# Sheet1.net
KiCad netlist of a schematic drawn in Altium Designer
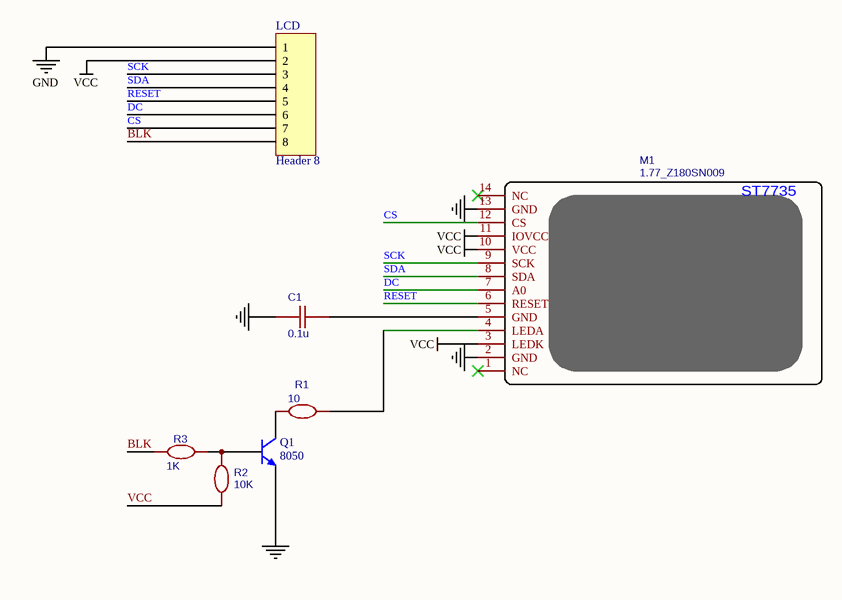
[diagram p0: Sheet1.SchDoc]

(export (version "E")
  (design (tool "Eeschema 10.0.6"))
  (components
    (comp (ref "C1")
      (value "0.1u")
      (footprint "0603")
      (fields (field (name "CONTRIBUTOR") "LCEDA_Lib"))
      (libsource (lib "altium-import") (part "root_2_0.1u_"))
    )
    (comp (ref "LCD")
      (value "Header 8")
      (footprint "HDR1X8")
      (description "Header, 8-Pin")
      (fields (field (name "PUBLISHER") "Altium Limited"))
      (libsource (lib "Miscellaneous Connectors") (part "Header 8"))
    )
    (comp (ref "M1")
      (value "1.77_Z180SN009")
      (footprint "PCBComponent_1")
      (fields (field (name "CONTRIBUTOR") "私有工程"))
      (libsource (lib "altium-import") (part "root_0_1.77_Z180SN009_"))
    )
    (comp (ref "Q1")
      (value "8050")
      (footprint "PCBComponent_1 - duplicate")
      (description "NPN General Purpose Amplifier")
      (fields (field (name "PUBLISHER") "Altium Limited"))
      (libsource (lib "Miscellaneous Devices") (part "2N3904"))
    )
    (comp (ref "R1")
      (value "10")
      (footprint "0603")
      (fields (field (name "CONTRIBUTOR") "LCEDA_Lib"))
      (libsource (lib "altium-import") (part "root_0_180R_"))
    )
    (comp (ref "R2")
      (value "10K")
      (footprint "0603")
      (fields (field (name "CONTRIBUTOR") "LCEDA_Lib"))
      (libsource (lib "altium-import") (part "root_1_0R/10K_"))
    )
    (comp (ref "R3")
      (value "1K")
      (footprint "0603")
      (fields (field (name "CONTRIBUTOR") "LCEDA_Lib"))
      (libsource (lib "altium-import") (part "root_2_470R_"))
    )
  )
  (nets
    (net (code "1") (name "/BLK") (class "Default")
      (node (ref "LCD") (pin "8") (pinfunction "8_8") (pintype "passive"))
      (node (ref "R3") (pin "2") (pinfunction "2_2") (pintype "passive"))
    )
    (net (code "2") (name "/CS") (class "Default")
      (node (ref "LCD") (pin "7") (pinfunction "7_7") (pintype "passive"))
      (node (ref "M1") (pin "12") (pinfunction "CS_12") (pintype "passive"))
    )
    (net (code "3") (name "/DC") (class "Default")
      (node (ref "LCD") (pin "6") (pinfunction "6_6") (pintype "passive"))
      (node (ref "M1") (pin "7") (pinfunction "A0_7") (pintype "passive"))
    )
    (net (code "4") (name "/RESET") (class "Default")
      (node (ref "LCD") (pin "5") (pinfunction "5_5") (pintype "passive"))
      (node (ref "M1") (pin "6") (pinfunction "RESET_6") (pintype "passive"))
    )
    (net (code "5") (name "/SCK") (class "Default")
      (node (ref "LCD") (pin "3") (pinfunction "3_3") (pintype "passive"))
      (node (ref "M1") (pin "9") (pinfunction "SCK_9") (pintype "passive"))
    )
    (net (code "6") (name "/SDA") (class "Default")
      (node (ref "LCD") (pin "4") (pinfunction "4_4") (pintype "passive"))
      (node (ref "M1") (pin "8") (pinfunction "SDA_8") (pintype "passive"))
    )
    (net (code "7") (name "GND") (class "Default")
      (node (ref "C1") (pin "2") (pinfunction "2_2") (pintype "passive"))
      (node (ref "LCD") (pin "1") (pinfunction "1_1") (pintype "passive"))
      (node (ref "M1") (pin "13") (pinfunction "GND_13") (pintype "passive"))
      (node (ref "M1") (pin "2") (pinfunction "GND_2") (pintype "passive"))
      (node (ref "Q1") (pin "1") (pinfunction "E_1") (pintype "passive"))
    )
    (net (code "8") (name "Net-(C1-Pad1)") (class "Default")
      (node (ref "C1") (pin "1") (pinfunction "1_1") (pintype "passive"))
      (node (ref "M1") (pin "5") (pinfunction "GND_5") (pintype "passive"))
    )
    (net (code "9") (name "Net-(M1-LEDA)") (class "Default")
      (node (ref "M1") (pin "4") (pinfunction "LEDA_4") (pintype "passive"))
      (node (ref "R1") (pin "2") (pinfunction "2_2") (pintype "passive"))
    )
    (net (code "10") (name "Net-(Q1-B)") (class "Default")
      (node (ref "Q1") (pin "2") (pinfunction "B_2") (pintype "passive"))
      (node (ref "R2") (pin "2") (pinfunction "2_2") (pintype "passive"))
      (node (ref "R3") (pin "1") (pinfunction "1_1") (pintype "passive"))
    )
    (net (code "11") (name "Net-(Q1-C)") (class "Default")
      (node (ref "Q1") (pin "3") (pinfunction "C_3") (pintype "passive"))
      (node (ref "R1") (pin "1") (pinfunction "1_1") (pintype "passive"))
    )
    (net (code "12") (name "VCC") (class "Default")
      (node (ref "LCD") (pin "2") (pinfunction "2_2") (pintype "passive"))
      (node (ref "M1") (pin "10") (pinfunction "VCC_10") (pintype "passive"))
      (node (ref "M1") (pin "11") (pinfunction "IOVCC_11") (pintype "passive"))
      (node (ref "M1") (pin "3") (pinfunction "LEDK_3") (pintype "passive"))
      (node (ref "R2") (pin "1") (pinfunction "1_1") (pintype "passive"))
    )
    (net (code "13") (name "unconnected-(M1-NC-Pad1)") (class "Default")
      (node (ref "M1") (pin "1") (pinfunction "NC_1") (pintype "passive+no_connect"))
    )
    (net (code "14") (name "unconnected-(M1-NC-Pad14)") (class "Default")
      (node (ref "M1") (pin "14") (pinfunction "NC_14") (pintype "passive+no_connect"))
    )
  )
)
